# TiltyDuo.net
KiCad netlist of a schematic drawn in EAGLE
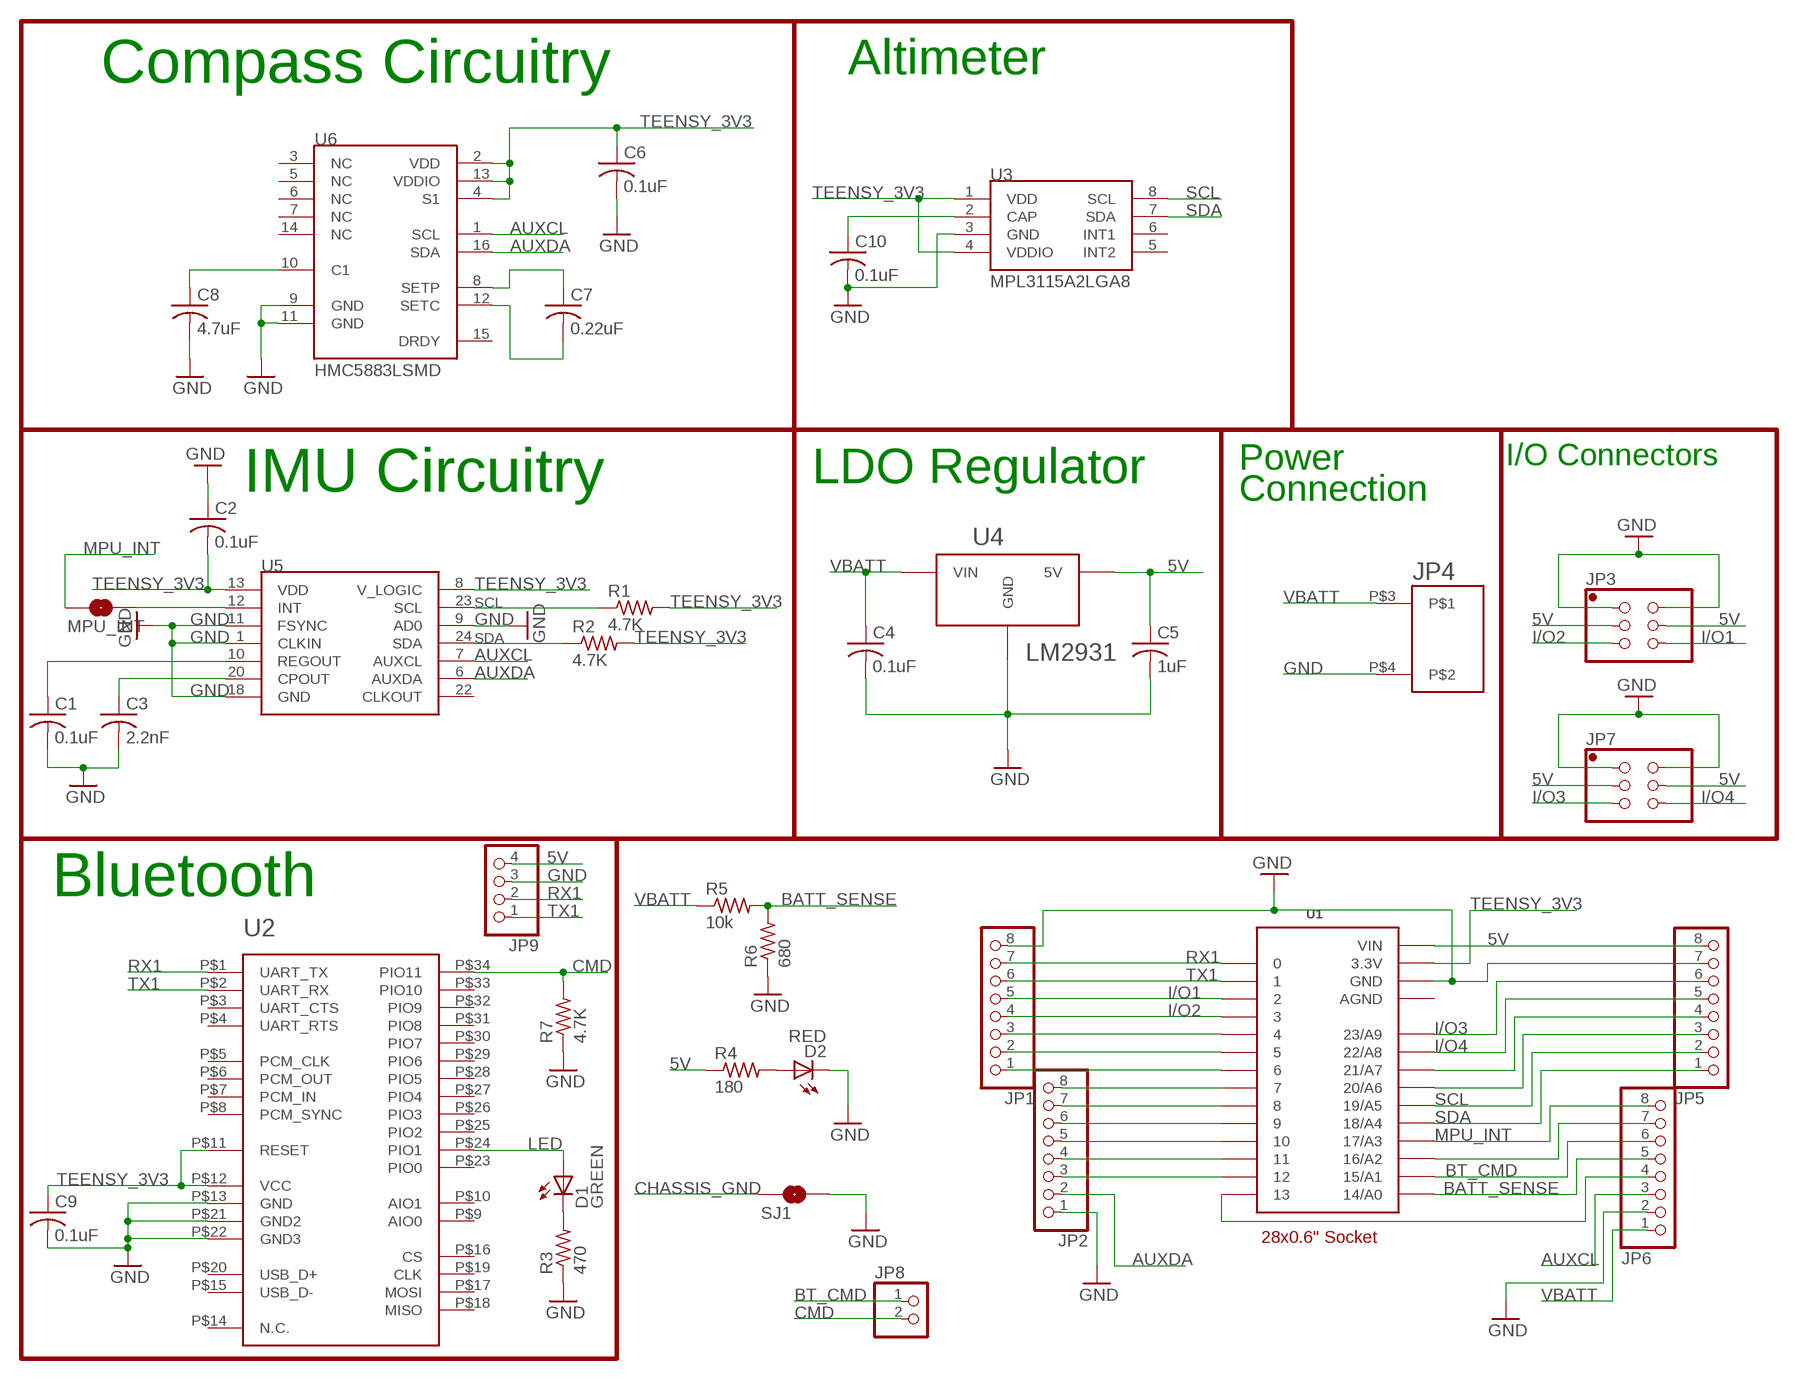
[diagram p0: schematic, sheet 1]

(export (version "E")
  (design (tool "Eeschema 10.0.6"))
  (components
    (comp (ref "C1")
      (value "0.1uF")
      (footprint "eagle-import:C0402")
      (libsource (lib "eagle-import") (part "C-USC0402"))
    )
    (comp (ref "C2")
      (value "0.1uF")
      (footprint "eagle-import:C0402")
      (libsource (lib "eagle-import") (part "C-USC0402"))
    )
    (comp (ref "C3")
      (value "2.2nF")
      (footprint "eagle-import:C0402")
      (libsource (lib "eagle-import") (part "C-USC0402"))
    )
    (comp (ref "C4")
      (value "0.1uF")
      (footprint "eagle-import:C0603")
      (libsource (lib "eagle-import") (part "C-USC0603"))
    )
    (comp (ref "C5")
      (value "1uF")
      (footprint "eagle-import:C0603")
      (libsource (lib "eagle-import") (part "C-USC0603"))
    )
    (comp (ref "C6")
      (value "0.1uF")
      (footprint "eagle-import:C0402")
      (libsource (lib "eagle-import") (part "C-USC0402"))
    )
    (comp (ref "C7")
      (value "0.22uF")
      (footprint "eagle-import:C0402")
      (libsource (lib "eagle-import") (part "C-USC0402"))
    )
    (comp (ref "C8")
      (value "4.7uF")
      (footprint "eagle-import:C0402")
      (libsource (lib "eagle-import") (part "C-USC0402"))
    )
    (comp (ref "C9")
      (value "0.1uF")
      (footprint "eagle-import:C0402")
      (libsource (lib "eagle-import") (part "C-USC0402"))
    )
    (comp (ref "C10")
      (value "0.1uF")
      (footprint "eagle-import:C0402")
      (libsource (lib "eagle-import") (part "C-USC0402"))
    )
    (comp (ref "D1")
      (value "GREEN")
      (footprint "eagle-import:LED-1206_NO_SS")
      (libsource (lib "eagle-import") (part "LED-GREEN1206_NO_SILK"))
    )
    (comp (ref "D2")
      (value "RED")
      (footprint "eagle-import:LED-1206_NO_SS")
      (libsource (lib "eagle-import") (part "LED-GREEN1206_NO_SILK"))
    )
    (comp (ref "JP1")
      (value "PINHD-1X81X08_NO_SILK")
      (footprint "eagle-import:1X08_NO_SS")
      (libsource (lib "eagle-import") (part "PINHD-1X81X08_NO_SILK"))
    )
    (comp (ref "JP2")
      (value "PINHD-1X81X08_NO_SILK")
      (footprint "eagle-import:1X08_NO_SS")
      (libsource (lib "eagle-import") (part "PINHD-1X81X08_NO_SILK"))
    )
    (comp (ref "JP3")
      (value "PINHD-2X32X03_NO_SILK")
      (footprint "eagle-import:2X03_NO_SS")
      (libsource (lib "eagle-import") (part "PINHD-2X32X03_NO_SILK"))
    )
    (comp (ref "JP4")
      (value "2-POS_SMD_TERM_BLOCK")
      (footprint "eagle-import:2-POS_SMD_TERMINAL_BLOCK")
      (libsource (lib "eagle-import") (part "2-POS_SMD_TERM_BLOCK"))
    )
    (comp (ref "JP5")
      (value "PINHD-1X81X08_NO_SILK")
      (footprint "eagle-import:1X08_NO_SS")
      (libsource (lib "eagle-import") (part "PINHD-1X81X08_NO_SILK"))
    )
    (comp (ref "JP6")
      (value "PINHD-1X81X08_NO_SILK")
      (footprint "eagle-import:1X08_NO_SS")
      (libsource (lib "eagle-import") (part "PINHD-1X81X08_NO_SILK"))
    )
    (comp (ref "JP7")
      (value "PINHD-2X32X03_NO_SILK")
      (footprint "eagle-import:2X03_NO_SS")
      (libsource (lib "eagle-import") (part "PINHD-2X32X03_NO_SILK"))
    )
    (comp (ref "JP8")
      (value "PINHD-1X21X02_NO_SILK")
      (footprint "eagle-import:1X02_NO_SS")
      (libsource (lib "eagle-import") (part "PINHD-1X21X02_NO_SILK"))
    )
    (comp (ref "JP9")
      (value "PINHD-1X4")
      (footprint "eagle-import:1X04")
      (libsource (lib "eagle-import") (part "PINHD-1X4"))
    )
    (comp (ref "MPU_INT")
      (value "SOLDERJUMPERNO")
      (footprint "eagle-import:SJ_2S-NO")
      (libsource (lib "eagle-import") (part "SOLDERJUMPERNO"))
    )
    (comp (ref "R1")
      (value "4.7K")
      (footprint "eagle-import:R0402")
      (libsource (lib "eagle-import") (part "R-US_R0402"))
    )
    (comp (ref "R2")
      (value "4.7K")
      (footprint "eagle-import:R0402")
      (libsource (lib "eagle-import") (part "R-US_R0402"))
    )
    (comp (ref "R3")
      (value "470")
      (footprint "eagle-import:R0603")
      (libsource (lib "eagle-import") (part "R-US_R0603"))
    )
    (comp (ref "R4")
      (value "180")
      (footprint "eagle-import:R0603")
      (libsource (lib "eagle-import") (part "R-US_R0603"))
    )
    (comp (ref "R5")
      (value "10k")
      (footprint "eagle-import:R0603")
      (libsource (lib "eagle-import") (part "R-US_R0603"))
    )
    (comp (ref "R6")
      (value "680")
      (footprint "eagle-import:R0603")
      (libsource (lib "eagle-import") (part "R-US_R0603"))
    )
    (comp (ref "R7")
      (value "4.7K")
      (footprint "eagle-import:R0402")
      (libsource (lib "eagle-import") (part "R-US_R0402"))
    )
    (comp (ref "SJ1")
      (value "SOLDERJUMPERNO")
      (footprint "eagle-import:SJ_2S-NO")
      (libsource (lib "eagle-import") (part "SOLDERJUMPERNO"))
    )
    (comp (ref "U1")
      (value "TEENSY_3.0_OUTER-PINS28-DIP_SOCKET")
      (footprint "eagle-import:28-DIP")
      (libsource (lib "eagle-import") (part "TEENSY_3.0_OUTER-PINS28-DIP_SOCKET"))
    )
    (comp (ref "U2")
      (value "HC-09_BREAKOUT")
      (footprint "eagle-import:HC-09_BREAKOUT")
      (libsource (lib "eagle-import") (part "HC-09_BREAKOUT"))
    )
    (comp (ref "U3")
      (value "MPL3115A2LGA8")
      (footprint "eagle-import:LGA8")
      (libsource (lib "eagle-import") (part "MPL3115A2LGA8"))
    )
    (comp (ref "U4")
      (value "LM2931")
      (footprint "eagle-import:TO263")
      (libsource (lib "eagle-import") (part "LM2931"))
    )
    (comp (ref "U5")
      (value "MPU-6050")
      (footprint "eagle-import:QFN-24")
      (libsource (lib "eagle-import") (part "MPU-6050"))
    )
    (comp (ref "U6")
      (value "HMC5883LSMD")
      (footprint "eagle-import:16LPCC")
      (libsource (lib "eagle-import") (part "HMC5883LSMD"))
    )
  )
  (nets
    (net (code "1") (name "/5V") (class "Default")
      (node (ref "C5") (pin "1") (pinfunction "1_1") (pintype "passive"))
      (node (ref "JP3") (pin "3") (pinfunction "3_3") (pintype "passive"))
      (node (ref "JP3") (pin "4") (pinfunction "4_4") (pintype "passive"))
      (node (ref "JP5") (pin "8") (pinfunction "8_8") (pintype "passive"))
      (node (ref "JP7") (pin "3") (pinfunction "3_3") (pintype "passive"))
      (node (ref "JP7") (pin "4") (pinfunction "4_4") (pintype "passive"))
      (node (ref "JP9") (pin "4") (pinfunction "4_4") (pintype "passive"))
      (node (ref "R4") (pin "1") (pinfunction "1_1") (pintype "passive"))
      (node (ref "U1") (pin "P$15") (pinfunction "VIN_P$15") (pintype "power_in"))
      (node (ref "U4") (pin "P$3") (pinfunction "5V_P$3") (pintype "bidirectional"))
    )
    (net (code "2") (name "/AGND") (class "Default")
      (node (ref "U1") (pin "P$16") (pinfunction "AGND_P$16") (pintype "power_in"))
    )
    (net (code "3") (name "/AUXCL") (class "Default")
      (node (ref "JP6") (pin "3") (pinfunction "3_3") (pintype "passive"))
      (node (ref "U5") (pin "7") (pinfunction "AUXCL_7") (pintype "bidirectional"))
      (node (ref "U6") (pin "1") (pinfunction "SCL_1") (pintype "bidirectional"))
    )
    (net (code "4") (name "/AUXDA") (class "Default")
      (node (ref "JP2") (pin "2") (pinfunction "2_2") (pintype "passive"))
      (node (ref "U5") (pin "6") (pinfunction "AUXDA_6") (pintype "bidirectional"))
      (node (ref "U6") (pin "16") (pinfunction "SDA_16") (pintype "bidirectional"))
    )
    (net (code "5") (name "/BATT_SENSE") (class "Default")
      (node (ref "JP6") (pin "5") (pinfunction "5_5") (pintype "passive"))
      (node (ref "R5") (pin "2") (pinfunction "2_2") (pintype "passive"))
      (node (ref "R6") (pin "2") (pinfunction "2_2") (pintype "passive"))
      (node (ref "U1") (pin "P$27") (pinfunction "14/A0_P$27") (pintype "bidirectional"))
    )
    (net (code "6") (name "/BT_CMD") (class "Default")
      (node (ref "JP6") (pin "6") (pinfunction "6_6") (pintype "passive"))
      (node (ref "JP8") (pin "1") (pinfunction "1_1") (pintype "passive"))
      (node (ref "U1") (pin "P$26") (pinfunction "15/A1_P$26") (pintype "bidirectional"))
    )
    (net (code "7") (name "/CHASSIS_GND") (class "Default")
      (node (ref "SJ1") (pin "1") (pinfunction "1_1") (pintype "passive"))
    )
    (net (code "8") (name "/CMD") (class "Default")
      (node (ref "JP8") (pin "2") (pinfunction "2_2") (pintype "passive"))
      (node (ref "R7") (pin "2") (pinfunction "2_2") (pintype "passive"))
      (node (ref "U2") (pin "P$34") (pinfunction "PIO11_P$34") (pintype "bidirectional"))
    )
    (net (code "9") (name "/I{slash}O1") (class "Default")
      (node (ref "JP1") (pin "5") (pinfunction "5_5") (pintype "passive"))
      (node (ref "JP3") (pin "6") (pinfunction "6_6") (pintype "passive"))
      (node (ref "U1") (pin "P$4") (pinfunction "2_P$4") (pintype "bidirectional"))
    )
    (net (code "10") (name "/I{slash}O2") (class "Default")
      (node (ref "JP1") (pin "4") (pinfunction "4_4") (pintype "passive"))
      (node (ref "JP3") (pin "5") (pinfunction "5_5") (pintype "passive"))
      (node (ref "U1") (pin "P$5") (pinfunction "3_P$5") (pintype "bidirectional"))
    )
    (net (code "11") (name "/I{slash}O3") (class "Default")
      (node (ref "JP5") (pin "6") (pinfunction "6_6") (pintype "passive"))
      (node (ref "JP7") (pin "5") (pinfunction "5_5") (pintype "passive"))
      (node (ref "U1") (pin "P$18") (pinfunction "23/A9_P$18") (pintype "bidirectional"))
    )
    (net (code "12") (name "/I{slash}O4") (class "Default")
      (node (ref "JP5") (pin "5") (pinfunction "5_5") (pintype "passive"))
      (node (ref "JP7") (pin "6") (pinfunction "6_6") (pintype "passive"))
      (node (ref "U1") (pin "P$19") (pinfunction "22/A8_P$19") (pintype "bidirectional"))
    )
    (net (code "13") (name "/LED") (class "Default")
      (node (ref "D1") (pin "A") (pinfunction "A_A") (pintype "passive"))
      (node (ref "U2") (pin "P$24") (pinfunction "PIO1_P$24") (pintype "bidirectional"))
    )
    (net (code "14") (name "/MPU_INT") (class "Default")
      (node (ref "JP6") (pin "8") (pinfunction "8_8") (pintype "passive"))
      (node (ref "MPU_INT") (pin "1") (pinfunction "1_1") (pintype "passive"))
      (node (ref "U1") (pin "P$24") (pinfunction "17/A3_P$24") (pintype "bidirectional"))
    )
    (net (code "15") (name "/RX1") (class "Default")
      (node (ref "JP1") (pin "7") (pinfunction "7_7") (pintype "passive"))
      (node (ref "JP9") (pin "2") (pinfunction "2_2") (pintype "passive"))
      (node (ref "U1") (pin "P$2") (pinfunction "0_P$2") (pintype "bidirectional"))
      (node (ref "U2") (pin "P$1") (pinfunction "UART_TX_P$1") (pintype "bidirectional"))
    )
    (net (code "16") (name "/SCL") (class "Default")
      (node (ref "JP5") (pin "2") (pinfunction "2_2") (pintype "passive"))
      (node (ref "R1") (pin "1") (pinfunction "1_1") (pintype "passive"))
      (node (ref "U1") (pin "P$22") (pinfunction "19/A5_P$22") (pintype "bidirectional"))
      (node (ref "U3") (pin "8") (pinfunction "SCL_8") (pintype "bidirectional"))
      (node (ref "U5") (pin "23") (pinfunction "SCL_23") (pintype "bidirectional"))
    )
    (net (code "17") (name "/SDA") (class "Default")
      (node (ref "JP5") (pin "1") (pinfunction "1_1") (pintype "passive"))
      (node (ref "R2") (pin "1") (pinfunction "1_1") (pintype "passive"))
      (node (ref "U1") (pin "P$23") (pinfunction "18/A4_P$23") (pintype "bidirectional"))
      (node (ref "U3") (pin "7") (pinfunction "SDA_7") (pintype "bidirectional"))
      (node (ref "U5") (pin "24") (pinfunction "SDA_24") (pintype "bidirectional"))
    )
    (net (code "18") (name "/TEENSY_3V3") (class "Default")
      (node (ref "C2") (pin "2") (pinfunction "2_2") (pintype "passive"))
      (node (ref "C6") (pin "1") (pinfunction "1_1") (pintype "passive"))
      (node (ref "C9") (pin "1") (pinfunction "1_1") (pintype "passive"))
      (node (ref "R1") (pin "2") (pinfunction "2_2") (pintype "passive"))
      (node (ref "R2") (pin "2") (pinfunction "2_2") (pintype "passive"))
      (node (ref "U1") (pin "P$17") (pinfunction "3.3V_P$17") (pintype "power_in"))
      (node (ref "U2") (pin "P$11") (pinfunction "RESET_P$11") (pintype "bidirectional"))
      (node (ref "U2") (pin "P$12") (pinfunction "VCC_P$12") (pintype "bidirectional"))
      (node (ref "U3") (pin "1") (pinfunction "VDD_1") (pintype "bidirectional"))
      (node (ref "U3") (pin "4") (pinfunction "VDDIO_4") (pintype "bidirectional"))
      (node (ref "U5") (pin "13") (pinfunction "VDD_13") (pintype "bidirectional"))
      (node (ref "U5") (pin "8") (pinfunction "V_LOGIC_8") (pintype "bidirectional"))
      (node (ref "U6") (pin "13") (pinfunction "VDDIO_13") (pintype "bidirectional"))
      (node (ref "U6") (pin "2") (pinfunction "VDD_2") (pintype "bidirectional"))
      (node (ref "U6") (pin "4") (pinfunction "S1_4") (pintype "bidirectional"))
    )
    (net (code "19") (name "/TX1") (class "Default")
      (node (ref "JP1") (pin "6") (pinfunction "6_6") (pintype "passive"))
      (node (ref "JP9") (pin "1") (pinfunction "1_1") (pintype "passive"))
      (node (ref "U1") (pin "P$3") (pinfunction "1_P$3") (pintype "bidirectional"))
      (node (ref "U2") (pin "P$2") (pinfunction "UART_RX_P$2") (pintype "bidirectional"))
    )
    (net (code "20") (name "/VBATT") (class "Default")
      (node (ref "C4") (pin "1") (pinfunction "1_1") (pintype "passive"))
      (node (ref "JP4") (pin "P$3") (pinfunction "P$1_P$3") (pintype "bidirectional"))
      (node (ref "JP6") (pin "1") (pinfunction "1_1") (pintype "passive"))
      (node (ref "R5") (pin "1") (pinfunction "1_1") (pintype "passive"))
      (node (ref "U4") (pin "P$2") (pinfunction "VIN_P$2") (pintype "bidirectional"))
    )
    (net (code "21") (name "GND") (class "Default")
      (node (ref "C1") (pin "2") (pinfunction "2_2") (pintype "passive"))
      (node (ref "C10") (pin "2") (pinfunction "2_2") (pintype "passive"))
      (node (ref "C2") (pin "1") (pinfunction "1_1") (pintype "passive"))
      (node (ref "C3") (pin "2") (pinfunction "2_2") (pintype "passive"))
      (node (ref "C4") (pin "2") (pinfunction "2_2") (pintype "passive"))
      (node (ref "C5") (pin "2") (pinfunction "2_2") (pintype "passive"))
      (node (ref "C6") (pin "2") (pinfunction "2_2") (pintype "passive"))
      (node (ref "C8") (pin "2") (pinfunction "2_2") (pintype "passive"))
      (node (ref "C9") (pin "2") (pinfunction "2_2") (pintype "passive"))
      (node (ref "D2") (pin "C") (pinfunction "C_C") (pintype "passive"))
      (node (ref "JP1") (pin "8") (pinfunction "8_8") (pintype "passive"))
      (node (ref "JP2") (pin "1") (pinfunction "1_1") (pintype "passive"))
      (node (ref "JP3") (pin "1") (pinfunction "1_1") (pintype "passive"))
      (node (ref "JP3") (pin "2") (pinfunction "2_2") (pintype "passive"))
      (node (ref "JP4") (pin "P$4") (pinfunction "P$2_P$4") (pintype "bidirectional"))
      (node (ref "JP5") (pin "7") (pinfunction "7_7") (pintype "passive"))
      (node (ref "JP6") (pin "2") (pinfunction "2_2") (pintype "passive"))
      (node (ref "JP7") (pin "1") (pinfunction "1_1") (pintype "passive"))
      (node (ref "JP7") (pin "2") (pinfunction "2_2") (pintype "passive"))
      (node (ref "JP9") (pin "3") (pinfunction "3_3") (pintype "passive"))
      (node (ref "R3") (pin "1") (pinfunction "1_1") (pintype "passive"))
      (node (ref "R6") (pin "1") (pinfunction "1_1") (pintype "passive"))
      (node (ref "R7") (pin "1") (pinfunction "1_1") (pintype "passive"))
      (node (ref "SJ1") (pin "2") (pinfunction "2_2") (pintype "passive"))
      (node (ref "U1") (pin "P$1") (pinfunction "GND_P$1") (pintype "power_in"))
      (node (ref "U2") (pin "P$13") (pinfunction "GND_P$13") (pintype "bidirectional"))
      (node (ref "U2") (pin "P$21") (pinfunction "GND2_P$21") (pintype "bidirectional"))
      (node (ref "U2") (pin "P$22") (pinfunction "GND3_P$22") (pintype "bidirectional"))
      (node (ref "U3") (pin "3") (pinfunction "GND_3") (pintype "bidirectional"))
      (node (ref "U4") (pin "P$1") (pinfunction "GND_P$1") (pintype "bidirectional"))
      (node (ref "U5") (pin "1") (pinfunction "CLKIN_1") (pintype "bidirectional"))
      (node (ref "U5") (pin "11") (pinfunction "FSYNC_11") (pintype "bidirectional"))
      (node (ref "U5") (pin "18") (pinfunction "GND_18") (pintype "bidirectional"))
      (node (ref "U5") (pin "9") (pinfunction "AD0_9") (pintype "bidirectional"))
      (node (ref "U6") (pin "11") (pinfunction "GND_11") (pintype "bidirectional"))
      (node (ref "U6") (pin "9") (pinfunction "GND_9") (pintype "bidirectional"))
    )
    (net (code "22") (name "Net-(D1-PadC)") (class "Default")
      (node (ref "D1") (pin "C") (pinfunction "C_C") (pintype "passive"))
      (node (ref "R3") (pin "2") (pinfunction "2_2") (pintype "passive"))
    )
    (net (code "23") (name "Net-(D2-PadA)") (class "Default")
      (node (ref "D2") (pin "A") (pinfunction "A_A") (pintype "passive"))
      (node (ref "R4") (pin "2") (pinfunction "2_2") (pintype "passive"))
    )
    (net (code "24") (name "Net-(U1-4)") (class "Default")
      (node (ref "JP1") (pin "3") (pinfunction "3_3") (pintype "passive"))
      (node (ref "U1") (pin "P$6") (pinfunction "4_P$6") (pintype "bidirectional"))
    )
    (net (code "25") (name "Net-(U1-5)") (class "Default")
      (node (ref "JP1") (pin "2") (pinfunction "2_2") (pintype "passive"))
      (node (ref "U1") (pin "P$7") (pinfunction "5_P$7") (pintype "bidirectional"))
    )
    (net (code "26") (name "Net-(U1-6)") (class "Default")
      (node (ref "JP1") (pin "1") (pinfunction "1_1") (pintype "passive"))
      (node (ref "U1") (pin "P$8") (pinfunction "6_P$8") (pintype "bidirectional"))
    )
    (net (code "27") (name "Net-(U1-7)") (class "Default")
      (node (ref "JP2") (pin "8") (pinfunction "8_8") (pintype "passive"))
      (node (ref "U1") (pin "P$9") (pinfunction "7_P$9") (pintype "bidirectional"))
    )
    (net (code "28") (name "Net-(U1-8)") (class "Default")
      (node (ref "JP2") (pin "7") (pinfunction "7_7") (pintype "passive"))
      (node (ref "U1") (pin "P$10") (pinfunction "8_P$10") (pintype "bidirectional"))
    )
    (net (code "29") (name "Net-(U1-9)") (class "Default")
      (node (ref "JP2") (pin "6") (pinfunction "6_6") (pintype "passive"))
      (node (ref "U1") (pin "P$11") (pinfunction "9_P$11") (pintype "bidirectional"))
    )
    (net (code "30") (name "Net-(U1-10)") (class "Default")
      (node (ref "JP2") (pin "5") (pinfunction "5_5") (pintype "passive"))
      (node (ref "U1") (pin "P$12") (pinfunction "10_P$12") (pintype "bidirectional"))
    )
    (net (code "31") (name "Net-(U1-11)") (class "Default")
      (node (ref "JP2") (pin "4") (pinfunction "4_4") (pintype "passive"))
      (node (ref "U1") (pin "P$13") (pinfunction "11_P$13") (pintype "bidirectional"))
    )
    (net (code "32") (name "Net-(U1-12)") (class "Default")
      (node (ref "JP2") (pin "3") (pinfunction "3_3") (pintype "passive"))
      (node (ref "U1") (pin "P$14") (pinfunction "12_P$14") (pintype "bidirectional"))
    )
    (net (code "33") (name "Net-(U1-13)") (class "Default")
      (node (ref "JP6") (pin "4") (pinfunction "4_4") (pintype "passive"))
      (node (ref "U1") (pin "P$28") (pinfunction "13_P$28") (pintype "bidirectional"))
    )
    (net (code "34") (name "Net-(U1-16{slash}A2)") (class "Default")
      (node (ref "JP6") (pin "7") (pinfunction "7_7") (pintype "passive"))
      (node (ref "U1") (pin "P$25") (pinfunction "16/A2_P$25") (pintype "bidirectional"))
    )
    (net (code "35") (name "Net-(U1-20{slash}A6)") (class "Default")
      (node (ref "JP5") (pin "3") (pinfunction "3_3") (pintype "passive"))
      (node (ref "U1") (pin "P$21") (pinfunction "20/A6_P$21") (pintype "bidirectional"))
    )
    (net (code "36") (name "Net-(U1-21{slash}A7)") (class "Default")
      (node (ref "JP5") (pin "4") (pinfunction "4_4") (pintype "passive"))
      (node (ref "U1") (pin "P$20") (pinfunction "21/A7_P$20") (pintype "bidirectional"))
    )
    (net (code "37") (name "Net-(U3-CAP)") (class "Default")
      (node (ref "C10") (pin "1") (pinfunction "1_1") (pintype "passive"))
      (node (ref "U3") (pin "2") (pinfunction "CAP_2") (pintype "bidirectional"))
    )
    (net (code "38") (name "Net-(U5-CPOUT)") (class "Default")
      (node (ref "C3") (pin "1") (pinfunction "1_1") (pintype "passive"))
      (node (ref "U5") (pin "20") (pinfunction "CPOUT_20") (pintype "bidirectional"))
    )
    (net (code "39") (name "Net-(U5-INT)") (class "Default")
      (node (ref "MPU_INT") (pin "2") (pinfunction "2_2") (pintype "passive"))
      (node (ref "U5") (pin "12") (pinfunction "INT_12") (pintype "bidirectional"))
    )
    (net (code "40") (name "Net-(U5-REGOUT)") (class "Default")
      (node (ref "C1") (pin "1") (pinfunction "1_1") (pintype "passive"))
      (node (ref "U5") (pin "10") (pinfunction "REGOUT_10") (pintype "bidirectional"))
    )
    (net (code "41") (name "Net-(U6-C1)") (class "Default")
      (node (ref "C8") (pin "1") (pinfunction "1_1") (pintype "passive"))
      (node (ref "U6") (pin "10") (pinfunction "C1_10") (pintype "bidirectional"))
    )
    (net (code "42") (name "Net-(U6-SETC)") (class "Default")
      (node (ref "C7") (pin "2") (pinfunction "2_2") (pintype "passive"))
      (node (ref "U6") (pin "12") (pinfunction "SETC_12") (pintype "bidirectional"))
    )
    (net (code "43") (name "Net-(U6-SETP)") (class "Default")
      (node (ref "C7") (pin "1") (pinfunction "1_1") (pintype "passive"))
      (node (ref "U6") (pin "8") (pinfunction "SETP_8") (pintype "bidirectional"))
    )
    (net (code "44") (name "unconnected-(U2-AIO0-PadP$9)") (class "Default")
      (node (ref "U2") (pin "P$9") (pinfunction "AIO0_P$9") (pintype "bidirectional"))
    )
    (net (code "45") (name "unconnected-(U2-AIO1-PadP$10)") (class "Default")
      (node (ref "U2") (pin "P$10") (pinfunction "AIO1_P$10") (pintype "bidirectional"))
    )
    (net (code "46") (name "unconnected-(U2-CLK-PadP$19)") (class "Default")
      (node (ref "U2") (pin "P$19") (pinfunction "CLK_P$19") (pintype "bidirectional"))
    )
    (net (code "47") (name "unconnected-(U2-CS-PadP$16)") (class "Default")
      (node (ref "U2") (pin "P$16") (pinfunction "CS_P$16") (pintype "bidirectional"))
    )
    (net (code "48") (name "unconnected-(U2-MISO-PadP$18)") (class "Default")
      (node (ref "U2") (pin "P$18") (pinfunction "MISO_P$18") (pintype "bidirectional"))
    )
    (net (code "49") (name "unconnected-(U2-MOSI-PadP$17)") (class "Default")
      (node (ref "U2") (pin "P$17") (pinfunction "MOSI_P$17") (pintype "bidirectional"))
    )
    (net (code "50") (name "unconnected-(U2-N.C.-PadP$14)") (class "Default")
      (node (ref "U2") (pin "P$14") (pinfunction "N.C._P$14") (pintype "bidirectional"))
    )
    (net (code "51") (name "unconnected-(U2-PCM_CLK-PadP$5)") (class "Default")
      (node (ref "U2") (pin "P$5") (pinfunction "PCM_CLK_P$5") (pintype "bidirectional"))
    )
    (net (code "52") (name "unconnected-(U2-PCM_IN-PadP$7)") (class "Default")
      (node (ref "U2") (pin "P$7") (pinfunction "PCM_IN_P$7") (pintype "bidirectional"))
    )
    (net (code "53") (name "unconnected-(U2-PCM_OUT-PadP$6)") (class "Default")
      (node (ref "U2") (pin "P$6") (pinfunction "PCM_OUT_P$6") (pintype "bidirectional"))
    )
    (net (code "54") (name "unconnected-(U2-PCM_SYNC-PadP$8)") (class "Default")
      (node (ref "U2") (pin "P$8") (pinfunction "PCM_SYNC_P$8") (pintype "bidirectional"))
    )
    (net (code "55") (name "unconnected-(U2-PIO0-PadP$23)") (class "Default")
      (node (ref "U2") (pin "P$23") (pinfunction "PIO0_P$23") (pintype "bidirectional"))
    )
    (net (code "56") (name "unconnected-(U2-PIO2-PadP$25)") (class "Default")
      (node (ref "U2") (pin "P$25") (pinfunction "PIO2_P$25") (pintype "bidirectional"))
    )
    (net (code "57") (name "unconnected-(U2-PIO3-PadP$26)") (class "Default")
      (node (ref "U2") (pin "P$26") (pinfunction "PIO3_P$26") (pintype "bidirectional"))
    )
    (net (code "58") (name "unconnected-(U2-PIO4-PadP$27)") (class "Default")
      (node (ref "U2") (pin "P$27") (pinfunction "PIO4_P$27") (pintype "bidirectional"))
    )
    (net (code "59") (name "unconnected-(U2-PIO5-PadP$28)") (class "Default")
      (node (ref "U2") (pin "P$28") (pinfunction "PIO5_P$28") (pintype "bidirectional"))
    )
    (net (code "60") (name "unconnected-(U2-PIO6-PadP$29)") (class "Default")
      (node (ref "U2") (pin "P$29") (pinfunction "PIO6_P$29") (pintype "bidirectional"))
    )
    (net (code "61") (name "unconnected-(U2-PIO7-PadP$30)") (class "Default")
      (node (ref "U2") (pin "P$30") (pinfunction "PIO7_P$30") (pintype "bidirectional"))
    )
    (net (code "62") (name "unconnected-(U2-PIO8-PadP$31)") (class "Default")
      (node (ref "U2") (pin "P$31") (pinfunction "PIO8_P$31") (pintype "bidirectional"))
    )
    (net (code "63") (name "unconnected-(U2-PIO9-PadP$32)") (class "Default")
      (node (ref "U2") (pin "P$32") (pinfunction "PIO9_P$32") (pintype "bidirectional"))
    )
    (net (code "64") (name "unconnected-(U2-PIO10-PadP$33)") (class "Default")
      (node (ref "U2") (pin "P$33") (pinfunction "PIO10_P$33") (pintype "bidirectional"))
    )
    (net (code "65") (name "unconnected-(U2-UART_CTS-PadP$3)") (class "Default")
      (node (ref "U2") (pin "P$3") (pinfunction "UART_CTS_P$3") (pintype "bidirectional"))
    )
    (net (code "66") (name "unconnected-(U2-UART_RTS-PadP$4)") (class "Default")
      (node (ref "U2") (pin "P$4") (pinfunction "UART_RTS_P$4") (pintype "bidirectional"))
    )
    (net (code "67") (name "unconnected-(U2-USB_D+-PadP$20)") (class "Default")
      (node (ref "U2") (pin "P$20") (pinfunction "USB_D+_P$20") (pintype "bidirectional"))
    )
    (net (code "68") (name "unconnected-(U2-USB_D--PadP$15)") (class "Default")
      (node (ref "U2") (pin "P$15") (pinfunction "USB_D-_P$15") (pintype "bidirectional"))
    )
    (net (code "69") (name "unconnected-(U3-INT1-Pad6)") (class "Default")
      (node (ref "U3") (pin "6") (pinfunction "INT1_6") (pintype "bidirectional"))
    )
    (net (code "70") (name "unconnected-(U3-INT2-Pad5)") (class "Default")
      (node (ref "U3") (pin "5") (pinfunction "INT2_5") (pintype "bidirectional"))
    )
    (net (code "71") (name "unconnected-(U5-CLKOUT-Pad22)") (class "Default")
      (node (ref "U5") (pin "22") (pinfunction "CLKOUT_22") (pintype "bidirectional"))
    )
    (net (code "72") (name "unconnected-(U6-DRDY-Pad15)") (class "Default")
      (node (ref "U6") (pin "15") (pinfunction "DRDY_15") (pintype "bidirectional"))
    )
    (net (code "73") (name "unconnected-(U6-NC-Pad3)") (class "Default")
      (node (ref "U6") (pin "3") (pinfunction "NC_3") (pintype "bidirectional"))
    )
    (net (code "74") (name "unconnected-(U6-NC-Pad5)") (class "Default")
      (node (ref "U6") (pin "5") (pinfunction "NC_5") (pintype "bidirectional"))
    )
    (net (code "75") (name "unconnected-(U6-NC-Pad6)") (class "Default")
      (node (ref "U6") (pin "6") (pinfunction "NC_6") (pintype "bidirectional"))
    )
    (net (code "76") (name "unconnected-(U6-NC-Pad7)") (class "Default")
      (node (ref "U6") (pin "7") (pinfunction "NC_7") (pintype "bidirectional"))
    )
    (net (code "77") (name "unconnected-(U6-NC-Pad14)") (class "Default")
      (node (ref "U6") (pin "14") (pinfunction "NC_14") (pintype "bidirectional"))
    )
  )
)
